# Handclap-TR808.net
KiCad netlist of a schematic drawn in EAGLE
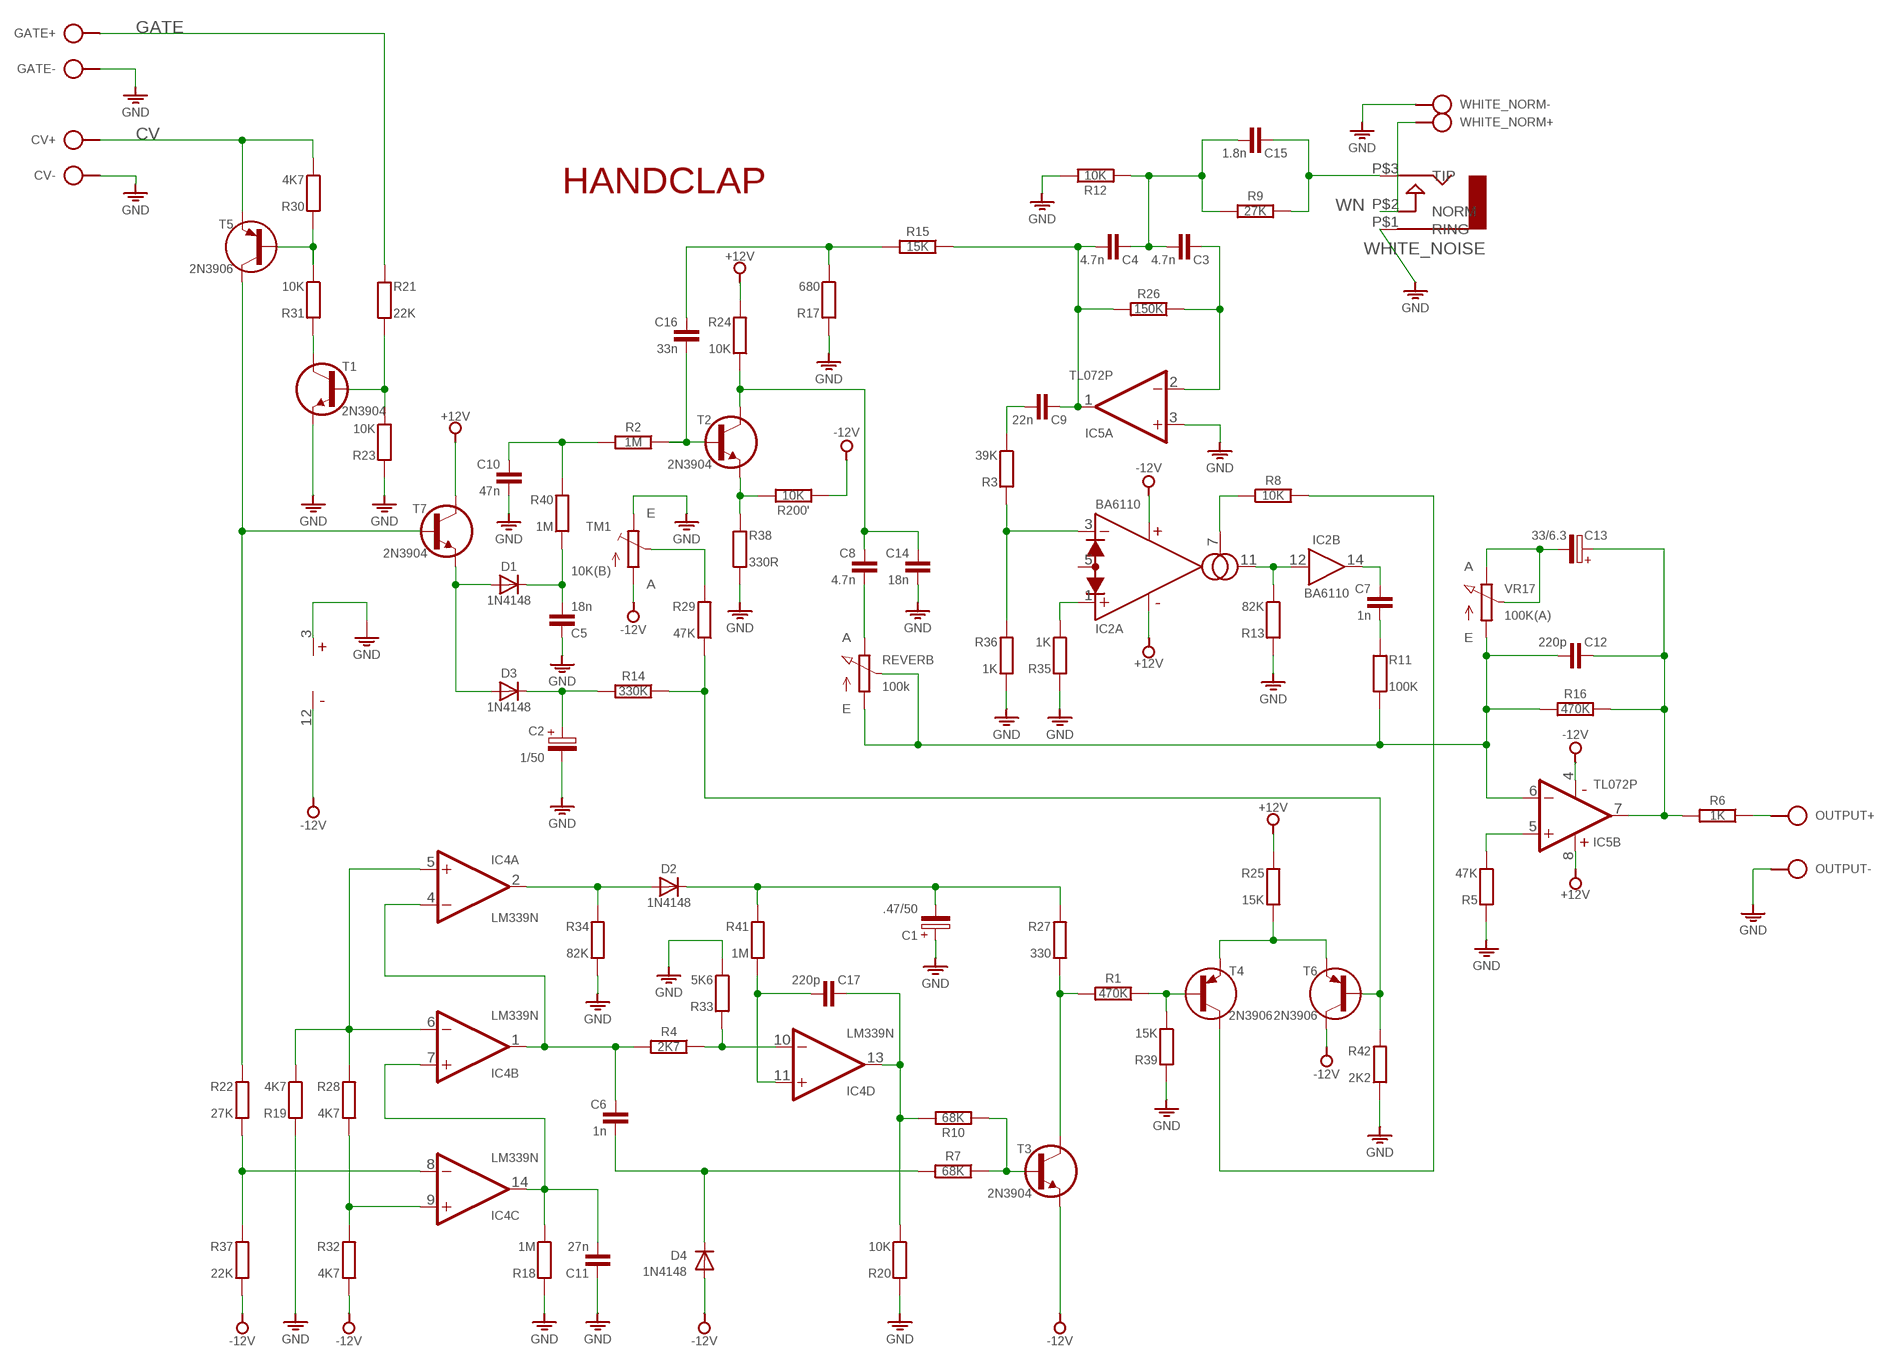
[diagram p0: schematic, sheet 1]

(export (version "E")
  (design (tool "Eeschema 10.0.6"))
  (components
    (comp (ref "C1")
      (value ".47/50")
      (footprint "eagle-import:E2,5-3_V")
      (libsource (lib "eagle-import") (part "CPOLE2,5-3/V"))
    )
    (comp (ref "C2")
      (value "1/50")
      (footprint "eagle-import:E2.5-4_V")
      (libsource (lib "eagle-import") (part "CPOLE2,5-4/V"))
    )
    (comp (ref "C3")
      (value "4.7n")
      (footprint "eagle-import:C050-020X044")
      (libsource (lib "eagle-import") (part "C-H050-020X044"))
    )
    (comp (ref "C4")
      (value "4.7n")
      (footprint "eagle-import:C050-020X044")
      (libsource (lib "eagle-import") (part "C-H050-020X044"))
    )
    (comp (ref "C5")
      (value "18n")
      (footprint "eagle-import:C050-020X044_V")
      (libsource (lib "eagle-import") (part "C050-020X044/V"))
    )
    (comp (ref "C6")
      (value "1n")
      (footprint "eagle-import:C050-020X044_V")
      (libsource (lib "eagle-import") (part "C050-020X044/V"))
    )
    (comp (ref "C7")
      (value "1n")
      (footprint "eagle-import:C050-020X044_V")
      (libsource (lib "eagle-import") (part "C050-020X044/V"))
    )
    (comp (ref "C8")
      (value "4.7n")
      (footprint "eagle-import:C050-020X044_V")
      (libsource (lib "eagle-import") (part "C050-020X044/V"))
    )
    (comp (ref "C9")
      (value "22n")
      (footprint "eagle-import:C050-020X044")
      (libsource (lib "eagle-import") (part "C-H050-020X044"))
    )
    (comp (ref "C10")
      (value "47n")
      (footprint "eagle-import:C050-020X044_V")
      (libsource (lib "eagle-import") (part "C050-020X044/V"))
    )
    (comp (ref "C11")
      (value "27n")
      (footprint "eagle-import:C050-020X044_V")
      (libsource (lib "eagle-import") (part "C050-020X044/V"))
    )
    (comp (ref "C12")
      (value "220p")
      (footprint "eagle-import:C050-020X044")
      (libsource (lib "eagle-import") (part "C-H050-020X044"))
    )
    (comp (ref "C13")
      (value "33/6.3")
      (footprint "eagle-import:E2,5-3")
      (libsource (lib "eagle-import") (part "CPOL-HE2,5-3"))
    )
    (comp (ref "C14")
      (value "18n")
      (footprint "eagle-import:C050-020X044_V")
      (libsource (lib "eagle-import") (part "C050-020X044/V"))
    )
    (comp (ref "C15")
      (value "1.8n")
      (footprint "eagle-import:C050-020X044")
      (libsource (lib "eagle-import") (part "C-H050-020X044"))
    )
    (comp (ref "C16")
      (value "33n")
      (footprint "eagle-import:C050-020X044_V")
      (libsource (lib "eagle-import") (part "C050-020X044/V"))
    )
    (comp (ref "C17")
      (value "220p")
      (footprint "eagle-import:C050-020X044")
      (libsource (lib "eagle-import") (part "C-H050-020X044"))
    )
    (comp (ref "CV")
      (value "SPAD+--+")
      (footprint "eagle-import:SPAD-+")
      (libsource (lib "eagle-import") (part "SPAD+--+"))
    )
    (comp (ref "D1")
      (value "1N4148")
      (footprint "eagle-import:DO34-10")
      (libsource (lib "eagle-import") (part "DIODE-HDO34-10"))
    )
    (comp (ref "D2")
      (value "1N4148")
      (footprint "eagle-import:DO34-2,5-A_V")
      (libsource (lib "eagle-import") (part "DIODE-HDO34-2,5-A/V"))
    )
    (comp (ref "D3")
      (value "1N4148")
      (footprint "eagle-import:DO34-10")
      (libsource (lib "eagle-import") (part "DIODE-HDO34-10"))
    )
    (comp (ref "D4")
      (value "1N4148")
      (footprint "eagle-import:DO34-7V")
      (libsource (lib "eagle-import") (part "DIODE34-7V"))
    )
    (comp (ref "GATE")
      (value "SPAD+--+")
      (footprint "eagle-import:SPAD-+")
      (libsource (lib "eagle-import") (part "SPAD+--+"))
    )
    (comp (ref "IC2")
      (value "BA6110")
      (footprint "eagle-import:DIL16")
      (libsource (lib "eagle-import") (part "BA6110-DIL16"))
    )
    (comp (ref "IC4")
      (value "LM339N")
      (footprint "eagle-import:DIL14")
      (libsource (lib "eagle-import") (part "LM339N"))
    )
    (comp (ref "IC5")
      (value "TL072P")
      (footprint "eagle-import:DIL08")
      (libsource (lib "eagle-import") (part "TL072P"))
    )
    (comp (ref "OUTPUT")
      (value "SPAD+--+")
      (footprint "eagle-import:SPAD-+")
      (libsource (lib "eagle-import") (part "SPAD+--+"))
    )
    (comp (ref "PWR1")
      (value "-12V_GND_+12V-VCC-VEE")
      (footprint "eagle-import:SPAD-PWR-+GND-")
      (libsource (lib "eagle-import") (part "-12V_GND_+12V-VCC-VEE"))
    )
    (comp (ref "R1")
      (value "470K")
      (footprint "eagle-import:0204_10")
      (libsource (lib "eagle-import") (part "R-H0204/10"))
    )
    (comp (ref "R2")
      (value "1M")
      (footprint "eagle-import:0204_10")
      (libsource (lib "eagle-import") (part "R-H0204/10"))
    )
    (comp (ref "R3")
      (value "39K")
      (footprint "eagle-import:0204_10-V")
      (libsource (lib "eagle-import") (part "R0204/10-V"))
    )
    (comp (ref "R4")
      (value "2K7")
      (footprint "eagle-import:0204_10")
      (libsource (lib "eagle-import") (part "R-H0204/10"))
    )
    (comp (ref "R5")
      (value "47K")
      (footprint "eagle-import:0204_10-V")
      (libsource (lib "eagle-import") (part "R0204/10-V"))
    )
    (comp (ref "R6")
      (value "1K")
      (footprint "eagle-import:0204_10")
      (libsource (lib "eagle-import") (part "R-H0204/10"))
    )
    (comp (ref "R7")
      (value "68K")
      (footprint "eagle-import:0204_10")
      (libsource (lib "eagle-import") (part "R-H0204/10"))
    )
    (comp (ref "R8")
      (value "10K")
      (footprint "eagle-import:0204_10")
      (libsource (lib "eagle-import") (part "R-H0204/10"))
    )
    (comp (ref "R9")
      (value "27K")
      (footprint "eagle-import:0204_10")
      (libsource (lib "eagle-import") (part "R-H0204/10"))
    )
    (comp (ref "R10")
      (value "68K")
      (footprint "eagle-import:0204_10")
      (libsource (lib "eagle-import") (part "R-H0204/10"))
    )
    (comp (ref "R11")
      (value "100K")
      (footprint "eagle-import:0204_10-V")
      (libsource (lib "eagle-import") (part "R0204/10-V"))
    )
    (comp (ref "R12")
      (value "10K")
      (footprint "eagle-import:0204_10")
      (libsource (lib "eagle-import") (part "R-H0204/10"))
    )
    (comp (ref "R13")
      (value "82K")
      (footprint "eagle-import:0204_10-V")
      (libsource (lib "eagle-import") (part "R0204/10-V"))
    )
    (comp (ref "R14")
      (value "330K")
      (footprint "eagle-import:0204_10")
      (libsource (lib "eagle-import") (part "R-H0204/10"))
    )
    (comp (ref "R15")
      (value "15K")
      (footprint "eagle-import:0204_10")
      (libsource (lib "eagle-import") (part "R-H0204/10"))
    )
    (comp (ref "R16")
      (value "470K")
      (footprint "eagle-import:0204_10")
      (libsource (lib "eagle-import") (part "R-H0204/10"))
    )
    (comp (ref "R17")
      (value "680")
      (footprint "eagle-import:0204_10-V")
      (libsource (lib "eagle-import") (part "R0204/10-V"))
    )
    (comp (ref "R18")
      (value "1M")
      (footprint "eagle-import:0204_10-V")
      (libsource (lib "eagle-import") (part "R0204/10-V"))
    )
    (comp (ref "R19")
      (value "4K7")
      (footprint "eagle-import:0204_10-V")
      (libsource (lib "eagle-import") (part "R0204/10-V"))
    )
    (comp (ref "R20")
      (value "10K")
      (footprint "eagle-import:0204_10-V")
      (libsource (lib "eagle-import") (part "R0204/10-V"))
    )
    (comp (ref "R21")
      (value "22K")
      (footprint "eagle-import:0204_10-V")
      (libsource (lib "eagle-import") (part "R0204/10-V"))
    )
    (comp (ref "R22")
      (value "27K")
      (footprint "eagle-import:0204_10-V")
      (libsource (lib "eagle-import") (part "R0204/10-V"))
    )
    (comp (ref "R23")
      (value "10K")
      (footprint "eagle-import:0204_10-V")
      (libsource (lib "eagle-import") (part "R0204/10-V"))
    )
    (comp (ref "R24")
      (value "10K")
      (footprint "eagle-import:0204_10-V")
      (libsource (lib "eagle-import") (part "R0204/10-V"))
    )
    (comp (ref "R25")
      (value "15K")
      (footprint "eagle-import:0204_10-V")
      (libsource (lib "eagle-import") (part "R0204/10-V"))
    )
    (comp (ref "R26")
      (value "150K")
      (footprint "eagle-import:0204_10")
      (libsource (lib "eagle-import") (part "R-H0204/10"))
    )
    (comp (ref "R27")
      (value "330")
      (footprint "eagle-import:0204_10-V")
      (libsource (lib "eagle-import") (part "R0204/10-V"))
    )
    (comp (ref "R28")
      (value "4K7")
      (footprint "eagle-import:0204_10-V")
      (libsource (lib "eagle-import") (part "R0204/10-V"))
    )
    (comp (ref "R29")
      (value "47K")
      (footprint "eagle-import:0204_10-V")
      (libsource (lib "eagle-import") (part "R0204/10-V"))
    )
    (comp (ref "R30")
      (value "4K7")
      (footprint "eagle-import:0204_10-V")
      (libsource (lib "eagle-import") (part "R0204/10-V"))
    )
    (comp (ref "R31")
      (value "10K")
      (footprint "eagle-import:0204_10-V")
      (libsource (lib "eagle-import") (part "R0204/10-V"))
    )
    (comp (ref "R32")
      (value "4K7")
      (footprint "eagle-import:0204_10-V")
      (libsource (lib "eagle-import") (part "R0204/10-V"))
    )
    (comp (ref "R33")
      (value "5K6")
      (footprint "eagle-import:0204_10-V")
      (libsource (lib "eagle-import") (part "R0204/10-V"))
    )
    (comp (ref "R34")
      (value "82K")
      (footprint "eagle-import:0204_10-V")
      (libsource (lib "eagle-import") (part "R0204/10-V"))
    )
    (comp (ref "R35")
      (value "1K")
      (footprint "eagle-import:0204_10-V")
      (libsource (lib "eagle-import") (part "R0204/10-V"))
    )
    (comp (ref "R36")
      (value "1K")
      (footprint "eagle-import:0204_10-V")
      (libsource (lib "eagle-import") (part "R0204/10-V"))
    )
    (comp (ref "R37")
      (value "22K")
      (footprint "eagle-import:0204_10-V")
      (libsource (lib "eagle-import") (part "R0204/10-V"))
    )
    (comp (ref "R38")
      (value "330R")
      (footprint "eagle-import:0204_10-V")
      (libsource (lib "eagle-import") (part "R0204/10-V"))
    )
    (comp (ref "R39")
      (value "15K")
      (footprint "eagle-import:0204_10-V")
      (libsource (lib "eagle-import") (part "R0204/10-V"))
    )
    (comp (ref "R40")
      (value "1M")
      (footprint "eagle-import:0204_10-V")
      (libsource (lib "eagle-import") (part "R0204/10-V"))
    )
    (comp (ref "R41")
      (value "1M")
      (footprint "eagle-import:0204_10-V")
      (libsource (lib "eagle-import") (part "R0204/10-V"))
    )
    (comp (ref "R42")
      (value "2K2")
      (footprint "eagle-import:0204_10-V")
      (libsource (lib "eagle-import") (part "R0204/10-V"))
    )
    (comp (ref "R200'")
      (value "10K")
      (footprint "eagle-import:0204_10")
      (libsource (lib "eagle-import") (part "R-H0204/10"))
    )
    (comp (ref "REVERB")
      (value "100k")
      (footprint "eagle-import:CONN-3P")
      (libsource (lib "eagle-import") (part "POT-3P"))
    )
    (comp (ref "T1")
      (value "2N3904")
      (footprint "eagle-import:TO92")
      (libsource (lib "eagle-import") (part "2N3904"))
    )
    (comp (ref "T2")
      (value "2N3904")
      (footprint "eagle-import:TO92")
      (libsource (lib "eagle-import") (part "2N3904"))
    )
    (comp (ref "T3")
      (value "2N3904")
      (footprint "eagle-import:TO92")
      (libsource (lib "eagle-import") (part "2N3904"))
    )
    (comp (ref "T4")
      (value "2N3906")
      (footprint "eagle-import:TO92")
      (libsource (lib "eagle-import") (part "2N3906"))
    )
    (comp (ref "T5")
      (value "2N3906")
      (footprint "eagle-import:TO92")
      (libsource (lib "eagle-import") (part "2N3906"))
    )
    (comp (ref "T6")
      (value "2N3906")
      (footprint "eagle-import:TO92")
      (libsource (lib "eagle-import") (part "2N3906"))
    )
    (comp (ref "T7")
      (value "2N3904")
      (footprint "eagle-import:TO92")
      (libsource (lib "eagle-import") (part "2N3904"))
    )
    (comp (ref "TM1")
      (value "10K(B)")
      (footprint "eagle-import:R-TRIM")
      (libsource (lib "eagle-import") (part "TRIMR-TRIM"))
    )
    (comp (ref "VR17")
      (value "100K(A)")
      (footprint "eagle-import:CONN-3P")
      (libsource (lib "eagle-import") (part "POT-3P"))
    )
    (comp (ref "WHITE_NOISE")
      (value "AUDIO-JACK")
      (footprint "eagle-import:ERTHENVAR-JACK-90DEG")
      (libsource (lib "eagle-import") (part "AUDIO-JACK"))
    )
    (comp (ref "WHITE_NORM")
      (value "SPAD+-+-")
      (footprint "eagle-import:SPAD+-")
      (libsource (lib "eagle-import") (part "SPAD+-+-"))
    )
  )
  (nets
    (net (code "1") (name "+12V") (class "Default")
      (node (ref "IC2") (pin "9") (pinfunction "V-_9") (pintype "power_in"))
      (node (ref "IC5") (pin "8") (pinfunction "V+_8") (pintype "power_in"))
      (node (ref "PWR1") (pin "VCC") (pinfunction "+12V_VCC") (pintype "power_in"))
      (node (ref "R24") (pin "1") (pinfunction "1_1") (pintype "passive"))
      (node (ref "R25") (pin "1") (pinfunction "1_1") (pintype "passive"))
      (node (ref "T7") (pin "3") (pinfunction "C_3") (pintype "passive"))
    )
    (net (code "2") (name "-12V") (class "Default")
      (node (ref "D4") (pin "A") (pinfunction "A_A") (pintype "passive"))
      (node (ref "IC2") (pin "15") (pinfunction "V+_15") (pintype "power_in"))
      (node (ref "IC4") (pin "12") (pinfunction "V-_12") (pintype "power_in"))
      (node (ref "IC5") (pin "4") (pinfunction "V-_4") (pintype "power_in"))
      (node (ref "PWR1") (pin "VEE") (pinfunction "-12V_VEE") (pintype "power_in"))
      (node (ref "R200'") (pin "2") (pinfunction "2_2") (pintype "passive"))
      (node (ref "R32") (pin "2") (pinfunction "2_2") (pintype "passive"))
      (node (ref "R37") (pin "2") (pinfunction "2_2") (pintype "passive"))
      (node (ref "T3") (pin "1") (pinfunction "E_1") (pintype "passive"))
      (node (ref "T6") (pin "3") (pinfunction "C_3") (pintype "passive"))
      (node (ref "TM1") (pin "1") (pinfunction "A_1") (pintype "passive"))
    )
    (net (code "3") (name "/CV") (class "Default")
      (node (ref "CV") (pin "2") (pinfunction "P$1_2") (pintype "passive"))
      (node (ref "R30") (pin "2") (pinfunction "2_2") (pintype "passive"))
      (node (ref "T5") (pin "1") (pinfunction "E_1") (pintype "passive"))
    )
    (net (code "4") (name "/GATE") (class "Default")
      (node (ref "GATE") (pin "2") (pinfunction "P$1_2") (pintype "passive"))
      (node (ref "R21") (pin "1") (pinfunction "1_1") (pintype "passive"))
    )
    (net (code "5") (name "/WN") (class "Default")
      (node (ref "C15") (pin "1") (pinfunction "1_1") (pintype "passive"))
      (node (ref "R9") (pin "1") (pinfunction "1_1") (pintype "passive"))
      (node (ref "WHITE_NOISE") (pin "P$3") (pinfunction "TIP_P$3") (pintype "bidirectional"))
    )
    (net (code "6") (name "GND") (class "Default")
      (node (ref "C1") (pin "+") (pinfunction "+_+") (pintype "passive"))
      (node (ref "C10") (pin "2") (pinfunction "2_2") (pintype "passive"))
      (node (ref "C11") (pin "1") (pinfunction "1_1") (pintype "passive"))
      (node (ref "C14") (pin "2") (pinfunction "2_2") (pintype "passive"))
      (node (ref "C2") (pin "-") (pinfunction "-_-") (pintype "passive"))
      (node (ref "C5") (pin "1") (pinfunction "1_1") (pintype "passive"))
      (node (ref "CV") (pin "1") (pinfunction "P$1_1") (pintype "passive"))
      (node (ref "GATE") (pin "1") (pinfunction "P$1_1") (pintype "passive"))
      (node (ref "IC4") (pin "3") (pinfunction "V+_3") (pintype "power_in"))
      (node (ref "IC5") (pin "3") (pinfunction "+IN_3") (pintype "input"))
      (node (ref "OUTPUT") (pin "1") (pinfunction "P$1_1") (pintype "passive"))
      (node (ref "PWR1") (pin "GND") (pinfunction "GND_GND") (pintype "power_in"))
      (node (ref "R12") (pin "1") (pinfunction "1_1") (pintype "passive"))
      (node (ref "R13") (pin "1") (pinfunction "1_1") (pintype "passive"))
      (node (ref "R17") (pin "1") (pinfunction "1_1") (pintype "passive"))
      (node (ref "R18") (pin "1") (pinfunction "1_1") (pintype "passive"))
      (node (ref "R19") (pin "1") (pinfunction "1_1") (pintype "passive"))
      (node (ref "R20") (pin "1") (pinfunction "1_1") (pintype "passive"))
      (node (ref "R23") (pin "1") (pinfunction "1_1") (pintype "passive"))
      (node (ref "R33") (pin "2") (pinfunction "2_2") (pintype "passive"))
      (node (ref "R34") (pin "2") (pinfunction "2_2") (pintype "passive"))
      (node (ref "R35") (pin "1") (pinfunction "1_1") (pintype "passive"))
      (node (ref "R36") (pin "2") (pinfunction "2_2") (pintype "passive"))
      (node (ref "R38") (pin "2") (pinfunction "2_2") (pintype "passive"))
      (node (ref "R39") (pin "1") (pinfunction "1_1") (pintype "passive"))
      (node (ref "R42") (pin "2") (pinfunction "2_2") (pintype "passive"))
      (node (ref "R5") (pin "1") (pinfunction "1_1") (pintype "passive"))
      (node (ref "T1") (pin "1") (pinfunction "E_1") (pintype "passive"))
      (node (ref "TM1") (pin "3") (pinfunction "E_3") (pintype "passive"))
      (node (ref "WHITE_NOISE") (pin "P$1") (pinfunction "RING_P$1") (pintype "bidirectional"))
      (node (ref "WHITE_NORM") (pin "1") (pinfunction "P$1_1") (pintype "passive"))
    )
    (net (code "7") (name "Net-(C1-Pad-)") (class "Default")
      (node (ref "C1") (pin "-") (pinfunction "-_-") (pintype "passive"))
      (node (ref "D2") (pin "C") (pinfunction "C_C") (pintype "passive"))
      (node (ref "R27") (pin "1") (pinfunction "1_1") (pintype "passive"))
      (node (ref "R41") (pin "1") (pinfunction "1_1") (pintype "passive"))
    )
    (net (code "8") (name "Net-(C2-Pad+)") (class "Default")
      (node (ref "C2") (pin "+") (pinfunction "+_+") (pintype "passive"))
      (node (ref "D3") (pin "C") (pinfunction "C_C") (pintype "passive"))
      (node (ref "R14") (pin "2") (pinfunction "2_2") (pintype "passive"))
    )
    (net (code "9") (name "Net-(C5-Pad2)") (class "Default")
      (node (ref "C5") (pin "2") (pinfunction "2_2") (pintype "passive"))
      (node (ref "D1") (pin "C") (pinfunction "C_C") (pintype "passive"))
      (node (ref "R40") (pin "2") (pinfunction "2_2") (pintype "passive"))
    )
    (net (code "10") (name "Net-(C6-Pad2)") (class "Default")
      (node (ref "C6") (pin "2") (pinfunction "2_2") (pintype "passive"))
      (node (ref "D4") (pin "C") (pinfunction "C_C") (pintype "passive"))
      (node (ref "R7") (pin "2") (pinfunction "2_2") (pintype "passive"))
    )
    (net (code "11") (name "Net-(C7-Pad2)") (class "Default")
      (node (ref "C7") (pin "2") (pinfunction "2_2") (pintype "passive"))
      (node (ref "R11") (pin "1") (pinfunction "1_1") (pintype "passive"))
    )
    (net (code "12") (name "Net-(C9-Pad2)") (class "Default")
      (node (ref "C9") (pin "2") (pinfunction "2_2") (pintype "passive"))
      (node (ref "R3") (pin "2") (pinfunction "2_2") (pintype "passive"))
    )
    (net (code "13") (name "Net-(C10-Pad1)") (class "Default")
      (node (ref "C10") (pin "1") (pinfunction "1_1") (pintype "passive"))
      (node (ref "R2") (pin "2") (pinfunction "2_2") (pintype "passive"))
      (node (ref "R40") (pin "1") (pinfunction "1_1") (pintype "passive"))
    )
    (net (code "14") (name "Net-(C15-Pad2)") (class "Default")
      (node (ref "C15") (pin "2") (pinfunction "2_2") (pintype "passive"))
      (node (ref "C3") (pin "2") (pinfunction "2_2") (pintype "passive"))
      (node (ref "C4") (pin "1") (pinfunction "1_1") (pintype "passive"))
      (node (ref "R12") (pin "2") (pinfunction "2_2") (pintype "passive"))
      (node (ref "R9") (pin "2") (pinfunction "2_2") (pintype "passive"))
    )
    (net (code "15") (name "Net-(C16-Pad1)") (class "Default")
      (node (ref "C16") (pin "1") (pinfunction "1_1") (pintype "passive"))
      (node (ref "R15") (pin "2") (pinfunction "2_2") (pintype "passive"))
      (node (ref "R17") (pin "2") (pinfunction "2_2") (pintype "passive"))
    )
    (net (code "16") (name "Net-(IC2B-+IN)") (class "Default")
      (node (ref "IC2") (pin "1") (pinfunction "+IN_1") (pintype "input"))
      (node (ref "R35") (pin "2") (pinfunction "2_2") (pintype "passive"))
    )
    (net (code "17") (name "Net-(IC2B--IN)") (class "Default")
      (node (ref "IC2") (pin "3") (pinfunction "-IN_3") (pintype "input"))
      (node (ref "R3") (pin "1") (pinfunction "1_1") (pintype "passive"))
      (node (ref "R36") (pin "1") (pinfunction "1_1") (pintype "passive"))
    )
    (net (code "18") (name "Net-(IC2B-AMP{slash}BIAS)") (class "Default")
      (node (ref "IC2") (pin "7") (pinfunction "AMP/BIAS_7") (pintype "input"))
      (node (ref "R8") (pin "1") (pinfunction "1_1") (pintype "passive"))
    )
    (net (code "19") (name "Net-(IC2B-OUT)") (class "Default")
      (node (ref "IC2") (pin "11") (pinfunction "OUT_11") (pintype "output"))
      (node (ref "IC2") (pin "12") (pinfunction "B_IN_12") (pintype "input"))
      (node (ref "R13") (pin "2") (pinfunction "2_2") (pintype "passive"))
    )
    (net (code "20") (name "Net-(IC2C-B_OUT)") (class "Default")
      (node (ref "C7") (pin "1") (pinfunction "1_1") (pintype "passive"))
      (node (ref "IC2") (pin "14") (pinfunction "B_OUT_14") (pintype "output"))
    )
    (net (code "21") (name "Net-(IC4B-+IN)") (class "Default")
      (node (ref "IC4") (pin "5") (pinfunction "+IN_5") (pintype "input"))
      (node (ref "IC4") (pin "6") (pinfunction "-IN_6") (pintype "input"))
      (node (ref "R19") (pin "2") (pinfunction "2_2") (pintype "passive"))
      (node (ref "R28") (pin "1") (pinfunction "1_1") (pintype "passive"))
    )
    (net (code "22") (name "Net-(IC4B--IN)") (class "Default")
      (node (ref "C6") (pin "1") (pinfunction "1_1") (pintype "passive"))
      (node (ref "IC4") (pin "1") (pinfunction "OUT_1") (pintype "output"))
      (node (ref "IC4") (pin "4") (pinfunction "-IN_4") (pintype "input"))
      (node (ref "R4") (pin "2") (pinfunction "2_2") (pintype "passive"))
    )
    (net (code "23") (name "Net-(IC4B-OUT)") (class "Default")
      (node (ref "D2") (pin "A") (pinfunction "A_A") (pintype "passive"))
      (node (ref "IC4") (pin "2") (pinfunction "OUT_2") (pintype "output"))
      (node (ref "R34") (pin "1") (pinfunction "1_1") (pintype "passive"))
    )
    (net (code "24") (name "Net-(IC4C-+IN)") (class "Default")
      (node (ref "C11") (pin "2") (pinfunction "2_2") (pintype "passive"))
      (node (ref "IC4") (pin "14") (pinfunction "OUT_14") (pintype "output"))
      (node (ref "IC4") (pin "7") (pinfunction "+IN_7") (pintype "input"))
      (node (ref "R18") (pin "2") (pinfunction "2_2") (pintype "passive"))
    )
    (net (code "25") (name "Net-(IC4D-+IN)") (class "Default")
      (node (ref "IC4") (pin "9") (pinfunction "+IN_9") (pintype "input"))
      (node (ref "R28") (pin "2") (pinfunction "2_2") (pintype "passive"))
      (node (ref "R32") (pin "1") (pinfunction "1_1") (pintype "passive"))
    )
    (net (code "26") (name "Net-(IC4D--IN)") (class "Default")
      (node (ref "IC4") (pin "8") (pinfunction "-IN_8") (pintype "input"))
      (node (ref "R22") (pin "2") (pinfunction "2_2") (pintype "passive"))
      (node (ref "R37") (pin "1") (pinfunction "1_1") (pintype "passive"))
    )
    (net (code "27") (name "Net-(IC4E-+IN)") (class "Default")
      (node (ref "C17") (pin "2") (pinfunction "2_2") (pintype "passive"))
      (node (ref "IC4") (pin "11") (pinfunction "+IN_11") (pintype "input"))
      (node (ref "R41") (pin "2") (pinfunction "2_2") (pintype "passive"))
    )
    (net (code "28") (name "Net-(IC4E--IN)") (class "Default")
      (node (ref "IC4") (pin "10") (pinfunction "-IN_10") (pintype "input"))
      (node (ref "R33") (pin "1") (pinfunction "1_1") (pintype "passive"))
      (node (ref "R4") (pin "1") (pinfunction "1_1") (pintype "passive"))
    )
    (net (code "29") (name "Net-(IC4E-OUT)") (class "Default")
      (node (ref "C17") (pin "1") (pinfunction "1_1") (pintype "passive"))
      (node (ref "IC4") (pin "13") (pinfunction "OUT_13") (pintype "output"))
      (node (ref "R10") (pin "1") (pinfunction "1_1") (pintype "passive"))
      (node (ref "R20") (pin "2") (pinfunction "2_2") (pintype "passive"))
    )
    (net (code "30") (name "Net-(IC5A--IN)") (class "Default")
      (node (ref "C3") (pin "1") (pinfunction "1_1") (pintype "passive"))
      (node (ref "IC5") (pin "2") (pinfunction "-IN_2") (pintype "input"))
      (node (ref "R26") (pin "1") (pinfunction "1_1") (pintype "passive"))
    )
    (net (code "31") (name "Net-(IC5A-OUT)") (class "Default")
      (node (ref "C4") (pin "2") (pinfunction "2_2") (pintype "passive"))
      (node (ref "C9") (pin "1") (pinfunction "1_1") (pintype "passive"))
      (node (ref "IC5") (pin "1") (pinfunction "OUT_1") (pintype "output"))
      (node (ref "R15") (pin "1") (pinfunction "1_1") (pintype "passive"))
      (node (ref "R26") (pin "2") (pinfunction "2_2") (pintype "passive"))
    )
    (net (code "32") (name "Net-(IC5B-+IN)") (class "Default")
      (node (ref "IC5") (pin "5") (pinfunction "+IN_5") (pintype "input"))
      (node (ref "R5") (pin "2") (pinfunction "2_2") (pintype "passive"))
    )
    (net (code "33") (name "Net-(IC5B--IN)") (class "Default")
      (node (ref "C12") (pin "2") (pinfunction "2_2") (pintype "passive"))
      (node (ref "IC5") (pin "6") (pinfunction "-IN_6") (pintype "input"))
      (node (ref "R11") (pin "2") (pinfunction "2_2") (pintype "passive"))
      (node (ref "R16") (pin "2") (pinfunction "2_2") (pintype "passive"))
      (node (ref "REVERB") (pin "1") (pinfunction "A_1") (pintype "passive"))
      (node (ref "REVERB") (pin "2") (pinfunction "S_2") (pintype "passive"))
      (node (ref "VR17") (pin "1") (pinfunction "A_1") (pintype "passive"))
    )
    (net (code "34") (name "Net-(IC5B-OUT)") (class "Default")
      (node (ref "C12") (pin "1") (pinfunction "1_1") (pintype "passive"))
      (node (ref "C13") (pin "+") (pinfunction "+_+") (pintype "passive"))
      (node (ref "IC5") (pin "7") (pinfunction "OUT_7") (pintype "output"))
      (node (ref "R16") (pin "1") (pinfunction "1_1") (pintype "passive"))
      (node (ref "R6") (pin "2") (pinfunction "2_2") (pintype "passive"))
    )
    (net (code "35") (name "Net-(OUTPUTA-P$1)") (class "Default")
      (node (ref "OUTPUT") (pin "2") (pinfunction "P$1_2") (pintype "passive"))
      (node (ref "R6") (pin "1") (pinfunction "1_1") (pintype "passive"))
    )
    (net (code "36") (name "Net-(REVERB-E)") (class "Default")
      (node (ref "C8") (pin "2") (pinfunction "2_2") (pintype "passive"))
      (node (ref "REVERB") (pin "3") (pinfunction "E_3") (pintype "passive"))
    )
    (net (code "37") (name "Net-(T1-B)") (class "Default")
      (node (ref "R21") (pin "2") (pinfunction "2_2") (pintype "passive"))
      (node (ref "R23") (pin "2") (pinfunction "2_2") (pintype "passive"))
      (node (ref "T1") (pin "2") (pinfunction "B_2") (pintype "passive"))
    )
    (net (code "38") (name "Net-(T1-C)") (class "Default")
      (node (ref "R31") (pin "1") (pinfunction "1_1") (pintype "passive"))
      (node (ref "T1") (pin "3") (pinfunction "C_3") (pintype "passive"))
    )
    (net (code "39") (name "Net-(T2-B)") (class "Default")
      (node (ref "C16") (pin "2") (pinfunction "2_2") (pintype "passive"))
      (node (ref "R2") (pin "1") (pinfunction "1_1") (pintype "passive"))
      (node (ref "T2") (pin "2") (pinfunction "B_2") (pintype "passive"))
    )
    (net (code "40") (name "Net-(T2-C)") (class "Default")
      (node (ref "C14") (pin "1") (pinfunction "1_1") (pintype "passive"))
      (node (ref "C8") (pin "1") (pinfunction "1_1") (pintype "passive"))
      (node (ref "R24") (pin "2") (pinfunction "2_2") (pintype "passive"))
      (node (ref "T2") (pin "3") (pinfunction "C_3") (pintype "passive"))
    )
    (net (code "41") (name "Net-(T2-E)") (class "Default")
      (node (ref "R200'") (pin "1") (pinfunction "1_1") (pintype "passive"))
      (node (ref "R38") (pin "1") (pinfunction "1_1") (pintype "passive"))
      (node (ref "T2") (pin "1") (pinfunction "E_1") (pintype "passive"))
    )
    (net (code "42") (name "Net-(T3-B)") (class "Default")
      (node (ref "R10") (pin "2") (pinfunction "2_2") (pintype "passive"))
      (node (ref "R7") (pin "1") (pinfunction "1_1") (pintype "passive"))
      (node (ref "T3") (pin "2") (pinfunction "B_2") (pintype "passive"))
    )
    (net (code "43") (name "Net-(T3-C)") (class "Default")
      (node (ref "R1") (pin "2") (pinfunction "2_2") (pintype "passive"))
      (node (ref "R27") (pin "2") (pinfunction "2_2") (pintype "passive"))
      (node (ref "T3") (pin "3") (pinfunction "C_3") (pintype "passive"))
    )
    (net (code "44") (name "Net-(T4-B)") (class "Default")
      (node (ref "R1") (pin "1") (pinfunction "1_1") (pintype "passive"))
      (node (ref "R39") (pin "2") (pinfunction "2_2") (pintype "passive"))
      (node (ref "T4") (pin "2") (pinfunction "B_2") (pintype "passive"))
    )
    (net (code "45") (name "Net-(T4-C)") (class "Default")
      (node (ref "R8") (pin "2") (pinfunction "2_2") (pintype "passive"))
      (node (ref "T4") (pin "3") (pinfunction "C_3") (pintype "passive"))
    )
    (net (code "46") (name "Net-(T4-E)") (class "Default")
      (node (ref "R25") (pin "2") (pinfunction "2_2") (pintype "passive"))
      (node (ref "T4") (pin "1") (pinfunction "E_1") (pintype "passive"))
      (node (ref "T6") (pin "1") (pinfunction "E_1") (pintype "passive"))
    )
    (net (code "47") (name "Net-(T5-B)") (class "Default")
      (node (ref "R30") (pin "1") (pinfunction "1_1") (pintype "passive"))
      (node (ref "R31") (pin "2") (pinfunction "2_2") (pintype "passive"))
      (node (ref "T5") (pin "2") (pinfunction "B_2") (pintype "passive"))
    )
    (net (code "48") (name "Net-(T5-C)") (class "Default")
      (node (ref "R22") (pin "1") (pinfunction "1_1") (pintype "passive"))
      (node (ref "T5") (pin "3") (pinfunction "C_3") (pintype "passive"))
      (node (ref "T7") (pin "2") (pinfunction "B_2") (pintype "passive"))
    )
    (net (code "49") (name "Net-(T6-B)") (class "Default")
      (node (ref "R14") (pin "1") (pinfunction "1_1") (pintype "passive"))
      (node (ref "R29") (pin "2") (pinfunction "2_2") (pintype "passive"))
      (node (ref "R42") (pin "1") (pinfunction "1_1") (pintype "passive"))
      (node (ref "T6") (pin "2") (pinfunction "B_2") (pintype "passive"))
    )
    (net (code "50") (name "Net-(T7-E)") (class "Default")
      (node (ref "D1") (pin "A") (pinfunction "A_A") (pintype "passive"))
      (node (ref "D3") (pin "A") (pinfunction "A_A") (pintype "passive"))
      (node (ref "T7") (pin "1") (pinfunction "E_1") (pintype "passive"))
    )
    (net (code "51") (name "Net-(TM1-S)") (class "Default")
      (node (ref "R29") (pin "1") (pinfunction "1_1") (pintype "passive"))
      (node (ref "TM1") (pin "2") (pinfunction "S_2") (pintype "passive"))
    )
    (net (code "52") (name "Net-(VR17-E)") (class "Default")
      (node (ref "C13") (pin "-") (pinfunction "-_-") (pintype "passive"))
      (node (ref "VR17") (pin "2") (pinfunction "S_2") (pintype "passive"))
      (node (ref "VR17") (pin "3") (pinfunction "E_3") (pintype "passive"))
    )
    (net (code "53") (name "Net-(WHITE_NOISE-NORM)") (class "Default")
      (node (ref "WHITE_NOISE") (pin "P$2") (pinfunction "NORM_P$2") (pintype "bidirectional"))
      (node (ref "WHITE_NORM") (pin "2") (pinfunction "P$1_2") (pintype "passive"))
    )
    (net (code "54") (name "unconnected-(IC2B-DIODE{slash}BIAS-Pad5)") (class "Default")
      (node (ref "IC2") (pin "5") (pinfunction "DIODE/BIAS_5") (pintype "passive"))
    )
  )
)
